# Pico_Primer_Kit_v1_0.net
KiCad netlist of a schematic drawn in EAGLE
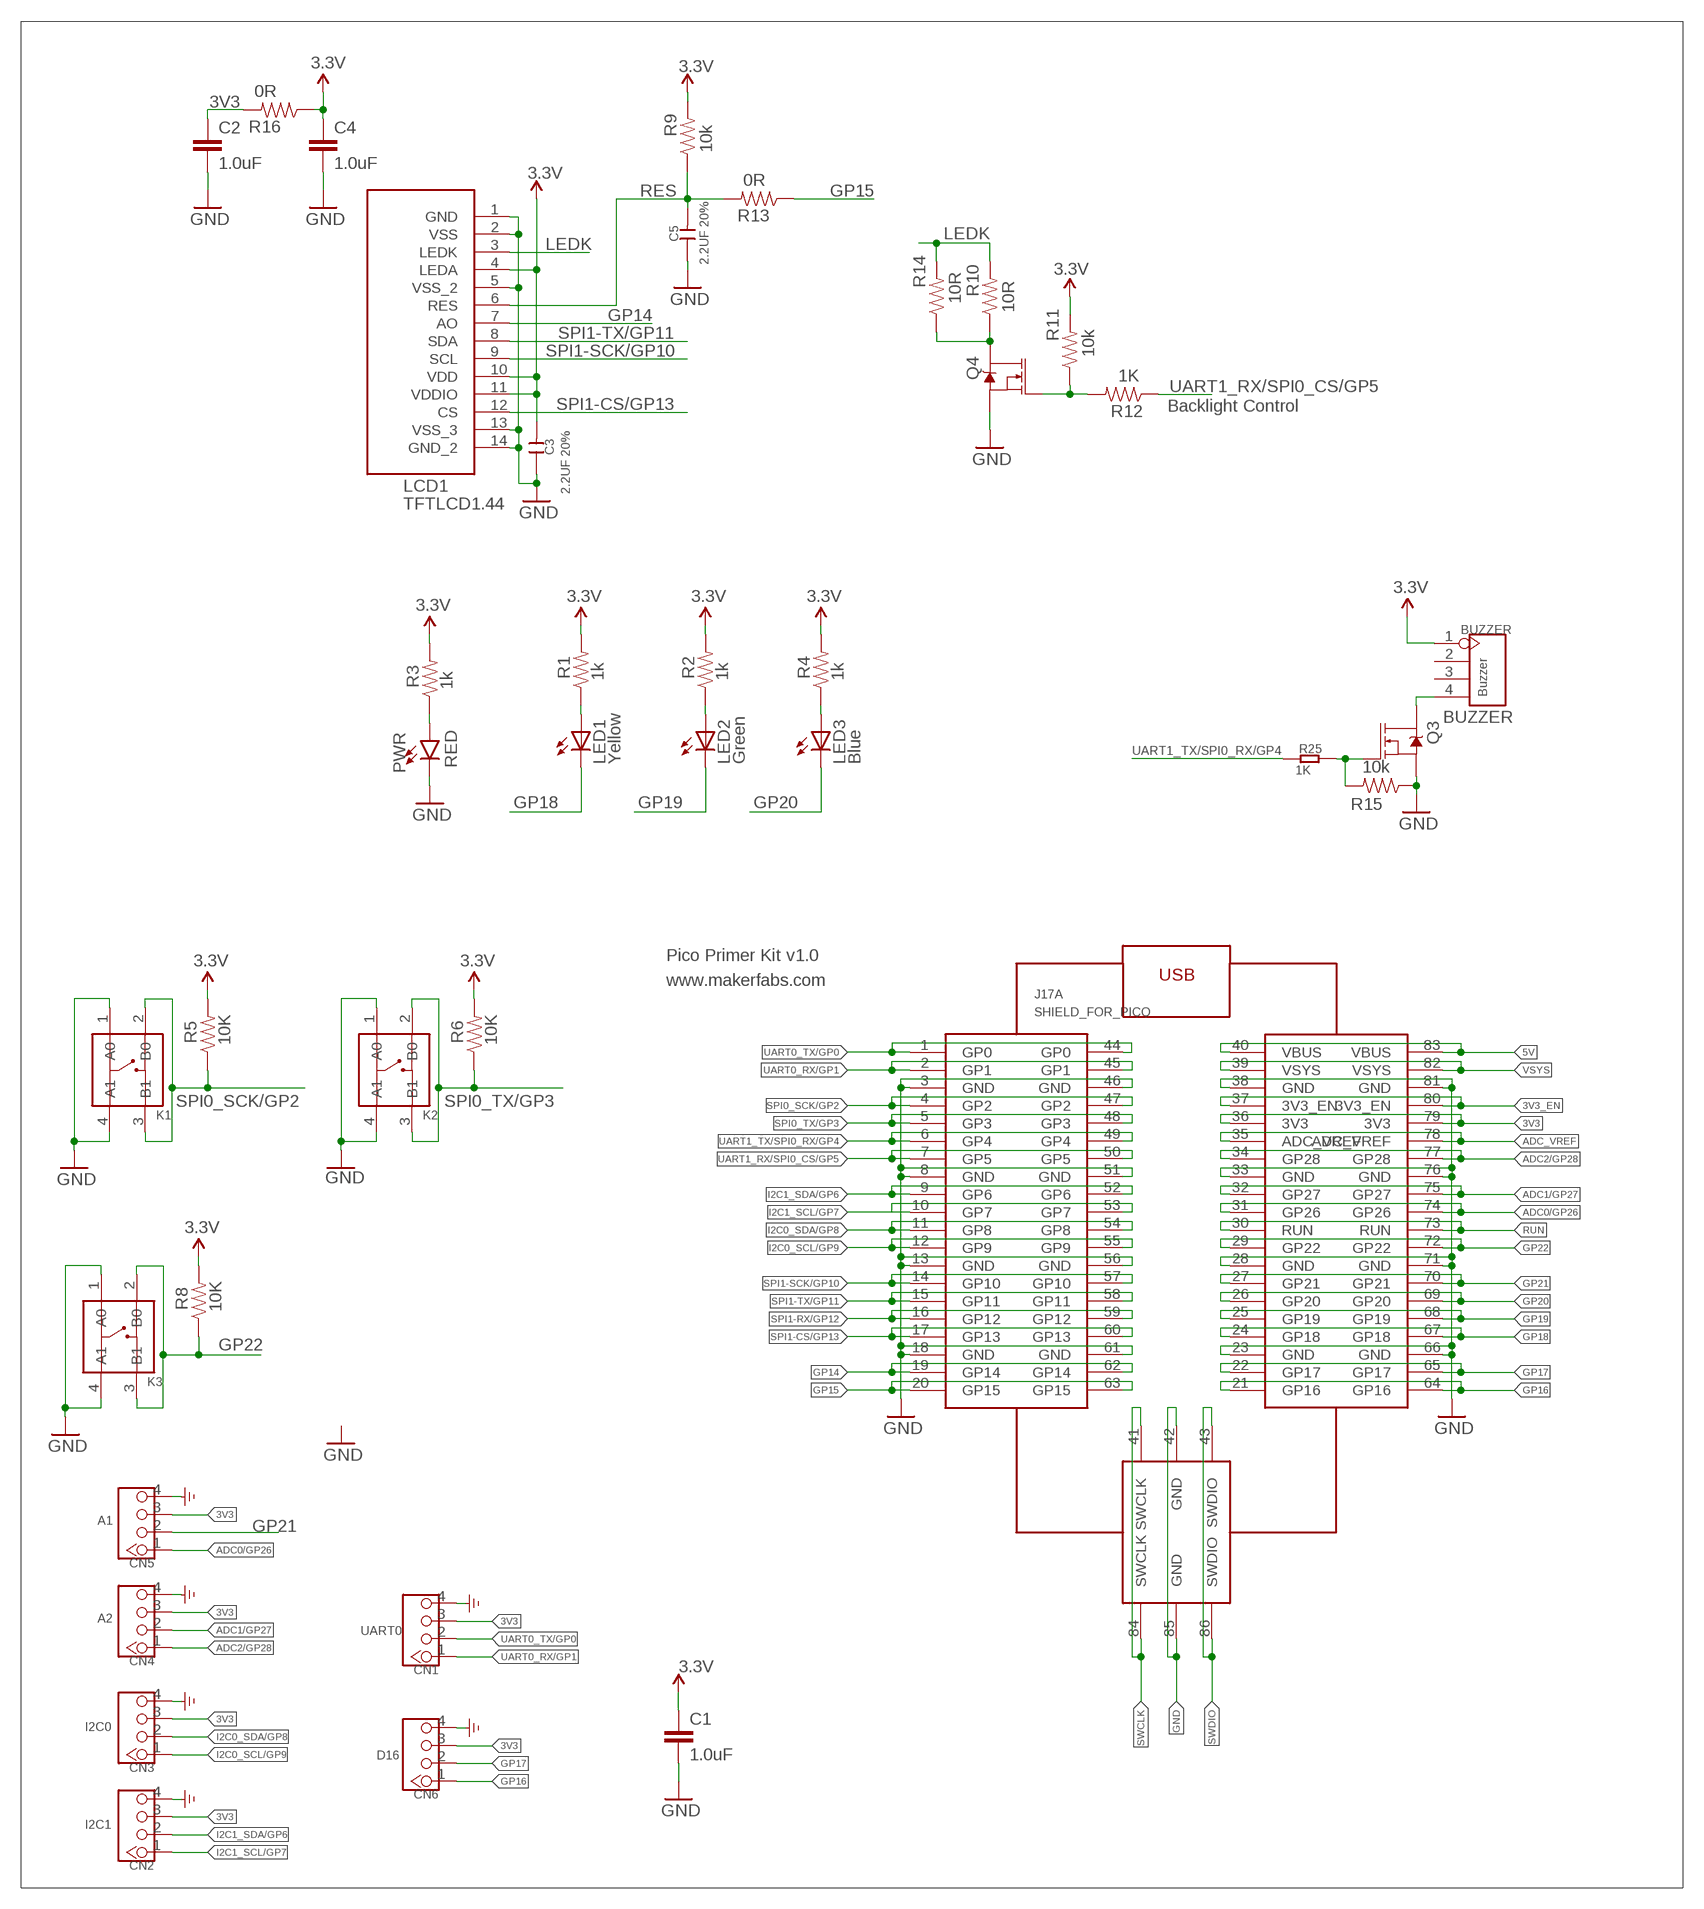
[diagram p0: schematic, sheet 1]

(export (version "E")
  (design (tool "Eeschema 10.0.6"))
  (components
    (comp (ref "BUZZER")
      (value "Buzzer")
      (footprint "eagle-import:4P-65_35ROUND")
      (libsource (lib "eagle-import") (part "HEADER-4P-60/35MILROUND"))
    )
    (comp (ref "C1")
      (value "1.0uF")
      (footprint "eagle-import:0603")
      (libsource (lib "eagle-import") (part "1.0UF-0603-16V-10%"))
    )
    (comp (ref "C2")
      (value "1.0uF")
      (footprint "eagle-import:0603")
      (libsource (lib "eagle-import") (part "1.0UF-0603-16V-10%"))
    )
    (comp (ref "C3")
      (value "2.2UF 20%")
      (footprint "eagle-import:0603")
      (libsource (lib "eagle-import") (part "C-0603"))
    )
    (comp (ref "C4")
      (value "1.0uF")
      (footprint "eagle-import:0603")
      (libsource (lib "eagle-import") (part "1.0UF-0603-16V-10%"))
    )
    (comp (ref "C5")
      (value "2.2UF 20%")
      (footprint "eagle-import:0603")
      (libsource (lib "eagle-import") (part "C-0603"))
    )
    (comp (ref "CN1")
      (value "UART0")
      (footprint "eagle-import:4P-2.0")
      (libsource (lib "eagle-import") (part "TWIG-4P-2.0-2.0"))
    )
    (comp (ref "CN2")
      (value "I2C1")
      (footprint "eagle-import:4P-2.0")
      (libsource (lib "eagle-import") (part "TWIG-4P-2.0-2.0"))
    )
    (comp (ref "CN3")
      (value "I2C0")
      (footprint "eagle-import:4P-2.0")
      (libsource (lib "eagle-import") (part "TWIG-4P-2.0-2.0"))
    )
    (comp (ref "CN4")
      (value "A2")
      (footprint "eagle-import:4P-2.0")
      (libsource (lib "eagle-import") (part "TWIG-4P-2.0-2.0"))
    )
    (comp (ref "CN5")
      (value "A1")
      (footprint "eagle-import:4P-2.0")
      (libsource (lib "eagle-import") (part "TWIG-4P-2.0-2.0"))
    )
    (comp (ref "CN6")
      (value "D16")
      (footprint "eagle-import:4P-2.0")
      (libsource (lib "eagle-import") (part "TWIG-4P-2.0-2.0"))
    )
    (comp (ref "J17A")
      (value "SHIELD_FOR_PICO")
      (footprint "eagle-import:SHIELD_FOR_PICO")
      (libsource (lib "eagle-import") (part "SHIELD_FOR_PICO"))
    )
    (comp (ref "K1")
      (value "BUTTON-4P-3100010P1")
      (footprint "eagle-import:4P-SMD-6.0X6.0X5.0H")
      (libsource (lib "eagle-import") (part "BUTTON-4P-3100010P1"))
    )
    (comp (ref "K2")
      (value "BUTTON-4P-3100010P1")
      (footprint "eagle-import:4P-SMD-6.0X6.0X5.0H")
      (libsource (lib "eagle-import") (part "BUTTON-4P-3100010P1"))
    )
    (comp (ref "K3")
      (value "BUTTON-4P-3100010P1")
      (footprint "eagle-import:4P-SMD-6.0X6.0X5.0H")
      (libsource (lib "eagle-import") (part "BUTTON-4P-3100010P1"))
    )
    (comp (ref "LCD1")
      (value "TFTLCD1.44")
      (footprint "eagle-import:TFTLCD1.44")
      (libsource (lib "eagle-import") (part "TFTLCD1.44"))
    )
    (comp (ref "LED1")
      (value "Yellow")
      (footprint "eagle-import:LED3MM")
      (libsource (lib "eagle-import") (part "LED3MM"))
    )
    (comp (ref "LED2")
      (value "Green")
      (footprint "eagle-import:LED3MM")
      (libsource (lib "eagle-import") (part "LED3MM"))
    )
    (comp (ref "LED3")
      (value "Blue")
      (footprint "eagle-import:LED3MM")
      (libsource (lib "eagle-import") (part "LED3MM"))
    )
    (comp (ref "PWR")
      (value "RED")
      (footprint "eagle-import:LED-0603")
      (libsource (lib "eagle-import") (part "LED-RED0603"))
    )
    (comp (ref "Q3")
      (value "220mA/50V/3.5Ω")
      (footprint "eagle-import:SOT23-3")
      (fields (field (name "PROD_ID") "TRANS-00830"))
      (libsource (lib "eagle-import") (part "MOSFET-NCH-BSS138"))
    )
    (comp (ref "Q4")
      (value "220mA/50V/3.5Ω")
      (footprint "eagle-import:SOT23-3")
      (fields (field (name "PROD_ID") "TRANS-00830"))
      (libsource (lib "eagle-import") (part "MOSFET-NCH-BSS138"))
    )
    (comp (ref "R1")
      (value "1k")
      (footprint "eagle-import:0603")
      (libsource (lib "eagle-import") (part "1KOHM-0603-1/10W-1%"))
    )
    (comp (ref "R2")
      (value "1k")
      (footprint "eagle-import:0603")
      (libsource (lib "eagle-import") (part "1KOHM-0603-1/10W-1%"))
    )
    (comp (ref "R3")
      (value "1k")
      (footprint "eagle-import:0603")
      (libsource (lib "eagle-import") (part "1KOHM-0603-1/10W-1%"))
    )
    (comp (ref "R4")
      (value "1k")
      (footprint "eagle-import:0603")
      (libsource (lib "eagle-import") (part "1KOHM-0603-1/10W-1%"))
    )
    (comp (ref "R5")
      (value "10K")
      (footprint "eagle-import:0603")
      (libsource (lib "eagle-import") (part "1KOHM-0603-1/10W-1%"))
    )
    (comp (ref "R6")
      (value "10K")
      (footprint "eagle-import:0603")
      (libsource (lib "eagle-import") (part "1KOHM-0603-1/10W-1%"))
    )
    (comp (ref "R8")
      (value "10K")
      (footprint "eagle-import:0603")
      (libsource (lib "eagle-import") (part "1KOHM-0603-1/10W-1%"))
    )
    (comp (ref "R9")
      (value "10k")
      (footprint "eagle-import:0603")
      (fields (field (name "PROD_ID") "RES-00824"))
      (libsource (lib "eagle-import") (part "10KOHM-0603-1/10W-1%"))
    )
    (comp (ref "R10")
      (value "10R")
      (footprint "eagle-import:0603")
      (fields (field (name "PROD_ID") "RES-00824"))
      (libsource (lib "eagle-import") (part "10KOHM-0603-1/10W-1%"))
    )
    (comp (ref "R11")
      (value "10k")
      (footprint "eagle-import:0603")
      (fields (field (name "PROD_ID") "RES-00824"))
      (libsource (lib "eagle-import") (part "10KOHM-0603-1/10W-1%"))
    )
    (comp (ref "R12")
      (value "1K")
      (footprint "eagle-import:0603")
      (fields (field (name "PROD_ID") "RES-00824"))
      (libsource (lib "eagle-import") (part "10KOHM-0603-1/10W-1%"))
    )
    (comp (ref "R13")
      (value "0R")
      (footprint "eagle-import:0603")
      (fields (field (name "PROD_ID") "RES-00824"))
      (libsource (lib "eagle-import") (part "10KOHM-0603-1/10W-1%"))
    )
    (comp (ref "R14")
      (value "10R")
      (footprint "eagle-import:0603")
      (fields (field (name "PROD_ID") "RES-00824"))
      (libsource (lib "eagle-import") (part "10KOHM-0603-1/10W-1%"))
    )
    (comp (ref "R15")
      (value "10k")
      (footprint "eagle-import:0603")
      (fields (field (name "PROD_ID") "RES-00824"))
      (libsource (lib "eagle-import") (part "10KOHM-0603-1/10W-1%"))
    )
    (comp (ref "R16")
      (value "0R")
      (footprint "eagle-import:0603")
      (fields (field (name "PROD_ID") "RES-00824"))
      (libsource (lib "eagle-import") (part "10KOHM-0603-1/10W-1%"))
    )
    (comp (ref "R25")
      (value "1K")
      (footprint "eagle-import:R0603")
      (libsource (lib "eagle-import") (part "R-0603"))
    )
  )
  (nets
    (net (code "1") (name "/LEDK") (class "Default")
      (node (ref "LCD1") (pin "3") (pinfunction "LEDK_3") (pintype "bidirectional"))
      (node (ref "R10") (pin "2") (pinfunction "2_2") (pintype "passive"))
      (node (ref "R14") (pin "2") (pinfunction "2_2") (pintype "passive"))
    )
    (net (code "2") (name "/RES") (class "Default")
      (node (ref "C5") (pin "2") (pinfunction "2_2") (pintype "passive"))
      (node (ref "LCD1") (pin "6") (pinfunction "RES_6") (pintype "bidirectional"))
      (node (ref "R13") (pin "2") (pinfunction "2_2") (pintype "passive"))
      (node (ref "R9") (pin "1") (pinfunction "1_1") (pintype "passive"))
    )
    (net (code "3") (name "3.3V") (class "Default")
      (node (ref "BUZZER") (pin "1") (pinfunction "P$1_1") (pintype "bidirectional"))
      (node (ref "C1") (pin "1") (pinfunction "1_1") (pintype "passive"))
      (node (ref "C3") (pin "2") (pinfunction "2_2") (pintype "passive"))
      (node (ref "C4") (pin "1") (pinfunction "1_1") (pintype "passive"))
      (node (ref "LCD1") (pin "10") (pinfunction "VDD_10") (pintype "bidirectional"))
      (node (ref "LCD1") (pin "11") (pinfunction "VDDIO_11") (pintype "bidirectional"))
      (node (ref "LCD1") (pin "4") (pinfunction "LEDA_4") (pintype "bidirectional"))
      (node (ref "R1") (pin "2") (pinfunction "2_2") (pintype "passive"))
      (node (ref "R11") (pin "2") (pinfunction "2_2") (pintype "passive"))
      (node (ref "R16") (pin "1") (pinfunction "1_1") (pintype "passive"))
      (node (ref "R2") (pin "2") (pinfunction "2_2") (pintype "passive"))
      (node (ref "R3") (pin "2") (pinfunction "2_2") (pintype "passive"))
      (node (ref "R4") (pin "2") (pinfunction "2_2") (pintype "passive"))
      (node (ref "R5") (pin "2") (pinfunction "2_2") (pintype "passive"))
      (node (ref "R6") (pin "2") (pinfunction "2_2") (pintype "passive"))
      (node (ref "R8") (pin "2") (pinfunction "2_2") (pintype "passive"))
      (node (ref "R9") (pin "2") (pinfunction "2_2") (pintype "passive"))
    )
    (net (code "4") (name "3V3") (class "Default")
      (node (ref "C2") (pin "1") (pinfunction "1_1") (pintype "passive"))
      (node (ref "CN1") (pin "3") (pinfunction "3_3") (pintype "bidirectional"))
      (node (ref "CN2") (pin "3") (pinfunction "3_3") (pintype "bidirectional"))
      (node (ref "CN3") (pin "3") (pinfunction "3_3") (pintype "bidirectional"))
      (node (ref "CN4") (pin "3") (pinfunction "3_3") (pintype "bidirectional"))
      (node (ref "CN5") (pin "3") (pinfunction "3_3") (pintype "bidirectional"))
      (node (ref "CN6") (pin "3") (pinfunction "3_3") (pintype "bidirectional"))
      (node (ref "J17A") (pin "36") (pinfunction "3V3_36") (pintype "bidirectional"))
      (node (ref "J17A") (pin "79") (pinfunction "3V3_79") (pintype "bidirectional"))
      (node (ref "R16") (pin "2") (pinfunction "2_2") (pintype "passive"))
    )
    (net (code "5") (name "3V3_EN") (class "Default")
      (node (ref "J17A") (pin "37") (pinfunction "3V3_EN_37") (pintype "bidirectional"))
      (node (ref "J17A") (pin "80") (pinfunction "3V3_EN_80") (pintype "bidirectional"))
    )
    (net (code "6") (name "5V") (class "Default")
      (node (ref "J17A") (pin "40") (pinfunction "VBUS_40") (pintype "bidirectional"))
      (node (ref "J17A") (pin "83") (pinfunction "VBUS_83") (pintype "bidirectional"))
    )
    (net (code "7") (name "ADC0{slash}GP26") (class "Default")
      (node (ref "CN5") (pin "1") (pinfunction "1_1") (pintype "bidirectional"))
      (node (ref "J17A") (pin "31") (pinfunction "GP26_31") (pintype "bidirectional"))
      (node (ref "J17A") (pin "74") (pinfunction "GP26_74") (pintype "bidirectional"))
    )
    (net (code "8") (name "ADC1{slash}GP27") (class "Default")
      (node (ref "CN4") (pin "2") (pinfunction "2_2") (pintype "bidirectional"))
      (node (ref "J17A") (pin "32") (pinfunction "GP27_32") (pintype "bidirectional"))
      (node (ref "J17A") (pin "75") (pinfunction "GP27_75") (pintype "bidirectional"))
    )
    (net (code "9") (name "ADC2{slash}GP28") (class "Default")
      (node (ref "CN4") (pin "1") (pinfunction "1_1") (pintype "bidirectional"))
      (node (ref "J17A") (pin "34") (pinfunction "GP28_34") (pintype "bidirectional"))
      (node (ref "J17A") (pin "77") (pinfunction "GP28_77") (pintype "bidirectional"))
    )
    (net (code "10") (name "ADC_VREF") (class "Default")
      (node (ref "J17A") (pin "35") (pinfunction "ADC_VREF_35") (pintype "bidirectional"))
      (node (ref "J17A") (pin "78") (pinfunction "ADC_VREF_78") (pintype "bidirectional"))
    )
    (net (code "11") (name "GND") (class "Default")
      (node (ref "C1") (pin "2") (pinfunction "2_2") (pintype "passive"))
      (node (ref "C2") (pin "2") (pinfunction "2_2") (pintype "passive"))
      (node (ref "C3") (pin "1") (pinfunction "1_1") (pintype "passive"))
      (node (ref "C4") (pin "2") (pinfunction "2_2") (pintype "passive"))
      (node (ref "C5") (pin "1") (pinfunction "1_1") (pintype "passive"))
      (node (ref "CN1") (pin "4") (pinfunction "4_4") (pintype "bidirectional"))
      (node (ref "CN2") (pin "4") (pinfunction "4_4") (pintype "bidirectional"))
      (node (ref "CN3") (pin "4") (pinfunction "4_4") (pintype "bidirectional"))
      (node (ref "CN4") (pin "4") (pinfunction "4_4") (pintype "bidirectional"))
      (node (ref "CN5") (pin "4") (pinfunction "4_4") (pintype "bidirectional"))
      (node (ref "CN6") (pin "4") (pinfunction "4_4") (pintype "bidirectional"))
      (node (ref "J17A") (pin "13") (pinfunction "GND_13") (pintype "bidirectional"))
      (node (ref "J17A") (pin "18") (pinfunction "GND_18") (pintype "bidirectional"))
      (node (ref "J17A") (pin "23") (pinfunction "GND_23") (pintype "bidirectional"))
      (node (ref "J17A") (pin "28") (pinfunction "GND_28") (pintype "bidirectional"))
      (node (ref "J17A") (pin "3") (pinfunction "GND_3") (pintype "bidirectional"))
      (node (ref "J17A") (pin "33") (pinfunction "GND_33") (pintype "bidirectional"))
      (node (ref "J17A") (pin "38") (pinfunction "GND_38") (pintype "bidirectional"))
      (node (ref "J17A") (pin "42") (pinfunction "GND_42") (pintype "bidirectional"))
      (node (ref "J17A") (pin "46") (pinfunction "GND_46") (pintype "bidirectional"))
      (node (ref "J17A") (pin "51") (pinfunction "GND_51") (pintype "bidirectional"))
      (node (ref "J17A") (pin "56") (pinfunction "GND_56") (pintype "bidirectional"))
      (node (ref "J17A") (pin "61") (pinfunction "GND_61") (pintype "bidirectional"))
      (node (ref "J17A") (pin "66") (pinfunction "GND_66") (pintype "bidirectional"))
      (node (ref "J17A") (pin "71") (pinfunction "GND_71") (pintype "bidirectional"))
      (node (ref "J17A") (pin "76") (pinfunction "GND_76") (pintype "bidirectional"))
      (node (ref "J17A") (pin "8") (pinfunction "GND_8") (pintype "bidirectional"))
      (node (ref "J17A") (pin "81") (pinfunction "GND_81") (pintype "bidirectional"))
      (node (ref "J17A") (pin "85") (pinfunction "GND_85") (pintype "bidirectional"))
      (node (ref "K1") (pin "1") (pinfunction "A0_1") (pintype "bidirectional"))
      (node (ref "K1") (pin "4") (pinfunction "A1_4") (pintype "bidirectional"))
      (node (ref "K2") (pin "1") (pinfunction "A0_1") (pintype "bidirectional"))
      (node (ref "K2") (pin "4") (pinfunction "A1_4") (pintype "bidirectional"))
      (node (ref "K3") (pin "1") (pinfunction "A0_1") (pintype "bidirectional"))
      (node (ref "K3") (pin "4") (pinfunction "A1_4") (pintype "bidirectional"))
      (node (ref "LCD1") (pin "1") (pinfunction "GND_1") (pintype "bidirectional"))
      (node (ref "LCD1") (pin "13") (pinfunction "VSS_3_13") (pintype "bidirectional"))
      (node (ref "LCD1") (pin "14") (pinfunction "GND_2_14") (pintype "bidirectional"))
      (node (ref "LCD1") (pin "2") (pinfunction "VSS_2") (pintype "bidirectional"))
      (node (ref "LCD1") (pin "5") (pinfunction "VSS_2_5") (pintype "bidirectional"))
      (node (ref "PWR") (pin "C") (pinfunction "C_C") (pintype "passive"))
      (node (ref "Q3") (pin "2") (pinfunction "S_2") (pintype "bidirectional"))
      (node (ref "Q4") (pin "2") (pinfunction "S_2") (pintype "bidirectional"))
      (node (ref "R15") (pin "1") (pinfunction "1_1") (pintype "passive"))
    )
    (net (code "12") (name "GP14") (class "Default")
      (node (ref "J17A") (pin "19") (pinfunction "GP14_19") (pintype "bidirectional"))
      (node (ref "J17A") (pin "62") (pinfunction "GP14_62") (pintype "bidirectional"))
      (node (ref "LCD1") (pin "7") (pinfunction "AO_7") (pintype "bidirectional"))
    )
    (net (code "13") (name "GP15") (class "Default")
      (node (ref "J17A") (pin "20") (pinfunction "GP15_20") (pintype "bidirectional"))
      (node (ref "J17A") (pin "63") (pinfunction "GP15_63") (pintype "bidirectional"))
      (node (ref "R13") (pin "1") (pinfunction "1_1") (pintype "passive"))
    )
    (net (code "14") (name "GP16") (class "Default")
      (node (ref "CN6") (pin "1") (pinfunction "1_1") (pintype "bidirectional"))
      (node (ref "J17A") (pin "21") (pinfunction "GP16_21") (pintype "bidirectional"))
      (node (ref "J17A") (pin "64") (pinfunction "GP16_64") (pintype "bidirectional"))
    )
    (net (code "15") (name "GP17") (class "Default")
      (node (ref "CN6") (pin "2") (pinfunction "2_2") (pintype "bidirectional"))
      (node (ref "J17A") (pin "22") (pinfunction "GP17_22") (pintype "bidirectional"))
      (node (ref "J17A") (pin "65") (pinfunction "GP17_65") (pintype "bidirectional"))
    )
    (net (code "16") (name "GP18") (class "Default")
      (node (ref "J17A") (pin "24") (pinfunction "GP18_24") (pintype "bidirectional"))
      (node (ref "J17A") (pin "67") (pinfunction "GP18_67") (pintype "bidirectional"))
      (node (ref "LED1") (pin "K") (pinfunction "C_K") (pintype "passive"))
    )
    (net (code "17") (name "GP19") (class "Default")
      (node (ref "J17A") (pin "25") (pinfunction "GP19_25") (pintype "bidirectional"))
      (node (ref "J17A") (pin "68") (pinfunction "GP19_68") (pintype "bidirectional"))
      (node (ref "LED2") (pin "K") (pinfunction "C_K") (pintype "passive"))
    )
    (net (code "18") (name "GP20") (class "Default")
      (node (ref "J17A") (pin "26") (pinfunction "GP20_26") (pintype "bidirectional"))
      (node (ref "J17A") (pin "69") (pinfunction "GP20_69") (pintype "bidirectional"))
      (node (ref "LED3") (pin "K") (pinfunction "C_K") (pintype "passive"))
    )
    (net (code "19") (name "GP21") (class "Default")
      (node (ref "CN5") (pin "2") (pinfunction "2_2") (pintype "bidirectional"))
      (node (ref "J17A") (pin "27") (pinfunction "GP21_27") (pintype "bidirectional"))
      (node (ref "J17A") (pin "70") (pinfunction "GP21_70") (pintype "bidirectional"))
    )
    (net (code "20") (name "GP22") (class "Default")
      (node (ref "J17A") (pin "29") (pinfunction "GP22_29") (pintype "bidirectional"))
      (node (ref "J17A") (pin "72") (pinfunction "GP22_72") (pintype "bidirectional"))
      (node (ref "K3") (pin "2") (pinfunction "B0_2") (pintype "bidirectional"))
      (node (ref "K3") (pin "3") (pinfunction "B1_3") (pintype "bidirectional"))
      (node (ref "R8") (pin "1") (pinfunction "1_1") (pintype "passive"))
    )
    (net (code "21") (name "I2C0_SCL{slash}GP9") (class "Default")
      (node (ref "CN3") (pin "1") (pinfunction "1_1") (pintype "bidirectional"))
      (node (ref "J17A") (pin "12") (pinfunction "GP9_12") (pintype "bidirectional"))
      (node (ref "J17A") (pin "55") (pinfunction "GP9_55") (pintype "bidirectional"))
    )
    (net (code "22") (name "I2C0_SDA{slash}GP8") (class "Default")
      (node (ref "CN3") (pin "2") (pinfunction "2_2") (pintype "bidirectional"))
      (node (ref "J17A") (pin "11") (pinfunction "GP8_11") (pintype "bidirectional"))
      (node (ref "J17A") (pin "54") (pinfunction "GP8_54") (pintype "bidirectional"))
    )
    (net (code "23") (name "I2C1_SCL{slash}GP7") (class "Default")
      (node (ref "CN2") (pin "1") (pinfunction "1_1") (pintype "bidirectional"))
      (node (ref "J17A") (pin "10") (pinfunction "GP7_10") (pintype "bidirectional"))
      (node (ref "J17A") (pin "53") (pinfunction "GP7_53") (pintype "bidirectional"))
    )
    (net (code "24") (name "I2C1_SDA{slash}GP6") (class "Default")
      (node (ref "CN2") (pin "2") (pinfunction "2_2") (pintype "bidirectional"))
      (node (ref "J17A") (pin "52") (pinfunction "GP6_52") (pintype "bidirectional"))
      (node (ref "J17A") (pin "9") (pinfunction "GP6_9") (pintype "bidirectional"))
    )
    (net (code "25") (name "Net-(BUZZER-P$4)") (class "Default")
      (node (ref "BUZZER") (pin "4") (pinfunction "P$4_4") (pintype "bidirectional"))
      (node (ref "Q3") (pin "3") (pinfunction "D_3") (pintype "bidirectional"))
    )
    (net (code "26") (name "Net-(LED1-PadA)") (class "Default")
      (node (ref "LED1") (pin "A") (pinfunction "A_A") (pintype "passive"))
      (node (ref "R1") (pin "1") (pinfunction "1_1") (pintype "passive"))
    )
    (net (code "27") (name "Net-(LED2-PadA)") (class "Default")
      (node (ref "LED2") (pin "A") (pinfunction "A_A") (pintype "passive"))
      (node (ref "R2") (pin "1") (pinfunction "1_1") (pintype "passive"))
    )
    (net (code "28") (name "Net-(LED3-PadA)") (class "Default")
      (node (ref "LED3") (pin "A") (pinfunction "A_A") (pintype "passive"))
      (node (ref "R4") (pin "1") (pinfunction "1_1") (pintype "passive"))
    )
    (net (code "29") (name "Net-(PWR-PadA)") (class "Default")
      (node (ref "PWR") (pin "A") (pinfunction "A_A") (pintype "passive"))
      (node (ref "R3") (pin "1") (pinfunction "1_1") (pintype "passive"))
    )
    (net (code "30") (name "Net-(Q3-G)") (class "Default")
      (node (ref "Q3") (pin "1") (pinfunction "G_1") (pintype "bidirectional"))
      (node (ref "R15") (pin "2") (pinfunction "2_2") (pintype "passive"))
      (node (ref "R25") (pin "2") (pinfunction "2_2") (pintype "passive"))
    )
    (net (code "31") (name "Net-(Q4-D)") (class "Default")
      (node (ref "Q4") (pin "3") (pinfunction "D_3") (pintype "bidirectional"))
      (node (ref "R10") (pin "1") (pinfunction "1_1") (pintype "passive"))
      (node (ref "R14") (pin "1") (pinfunction "1_1") (pintype "passive"))
    )
    (net (code "32") (name "Net-(Q4-G)") (class "Default")
      (node (ref "Q4") (pin "1") (pinfunction "G_1") (pintype "bidirectional"))
      (node (ref "R11") (pin "1") (pinfunction "1_1") (pintype "passive"))
      (node (ref "R12") (pin "2") (pinfunction "2_2") (pintype "passive"))
    )
    (net (code "33") (name "RUN") (class "Default")
      (node (ref "J17A") (pin "30") (pinfunction "RUN_30") (pintype "bidirectional"))
      (node (ref "J17A") (pin "73") (pinfunction "RUN_73") (pintype "bidirectional"))
    )
    (net (code "34") (name "SPI0_SCK{slash}GP2") (class "Default")
      (node (ref "J17A") (pin "4") (pinfunction "GP2_4") (pintype "bidirectional"))
      (node (ref "J17A") (pin "47") (pinfunction "GP2_47") (pintype "bidirectional"))
      (node (ref "K1") (pin "2") (pinfunction "B0_2") (pintype "bidirectional"))
      (node (ref "K1") (pin "3") (pinfunction "B1_3") (pintype "bidirectional"))
      (node (ref "R5") (pin "1") (pinfunction "1_1") (pintype "passive"))
    )
    (net (code "35") (name "SPI0_TX{slash}GP3") (class "Default")
      (node (ref "J17A") (pin "48") (pinfunction "GP3_48") (pintype "bidirectional"))
      (node (ref "J17A") (pin "5") (pinfunction "GP3_5") (pintype "bidirectional"))
      (node (ref "K2") (pin "2") (pinfunction "B0_2") (pintype "bidirectional"))
      (node (ref "K2") (pin "3") (pinfunction "B1_3") (pintype "bidirectional"))
      (node (ref "R6") (pin "1") (pinfunction "1_1") (pintype "passive"))
    )
    (net (code "36") (name "SPI1-CS{slash}GP13") (class "Default")
      (node (ref "J17A") (pin "17") (pinfunction "GP13_17") (pintype "bidirectional"))
      (node (ref "J17A") (pin "60") (pinfunction "GP13_60") (pintype "bidirectional"))
      (node (ref "LCD1") (pin "12") (pinfunction "CS_12") (pintype "bidirectional"))
    )
    (net (code "37") (name "SPI1-RX{slash}GP12") (class "Default")
      (node (ref "J17A") (pin "16") (pinfunction "GP12_16") (pintype "bidirectional"))
      (node (ref "J17A") (pin "59") (pinfunction "GP12_59") (pintype "bidirectional"))
    )
    (net (code "38") (name "SPI1-SCK{slash}GP10") (class "Default")
      (node (ref "J17A") (pin "14") (pinfunction "GP10_14") (pintype "bidirectional"))
      (node (ref "J17A") (pin "57") (pinfunction "GP10_57") (pintype "bidirectional"))
      (node (ref "LCD1") (pin "9") (pinfunction "SCL_9") (pintype "bidirectional"))
    )
    (net (code "39") (name "SPI1-TX{slash}GP11") (class "Default")
      (node (ref "J17A") (pin "15") (pinfunction "GP11_15") (pintype "bidirectional"))
      (node (ref "J17A") (pin "58") (pinfunction "GP11_58") (pintype "bidirectional"))
      (node (ref "LCD1") (pin "8") (pinfunction "SDA_8") (pintype "bidirectional"))
    )
    (net (code "40") (name "SWCLK") (class "Default")
      (node (ref "J17A") (pin "41") (pinfunction "SWCLK_41") (pintype "bidirectional"))
      (node (ref "J17A") (pin "84") (pinfunction "SWCLK_84") (pintype "bidirectional"))
    )
    (net (code "41") (name "SWDIO") (class "Default")
      (node (ref "J17A") (pin "43") (pinfunction "SWDIO_43") (pintype "bidirectional"))
      (node (ref "J17A") (pin "86") (pinfunction "SWDIO_86") (pintype "bidirectional"))
    )
    (net (code "42") (name "UART0_RX{slash}GP1") (class "Default")
      (node (ref "CN1") (pin "1") (pinfunction "1_1") (pintype "bidirectional"))
      (node (ref "J17A") (pin "2") (pinfunction "GP1_2") (pintype "bidirectional"))
      (node (ref "J17A") (pin "45") (pinfunction "GP1_45") (pintype "bidirectional"))
    )
    (net (code "43") (name "UART0_TX{slash}GP0") (class "Default")
      (node (ref "CN1") (pin "2") (pinfunction "2_2") (pintype "bidirectional"))
      (node (ref "J17A") (pin "1") (pinfunction "GP0_1") (pintype "bidirectional"))
      (node (ref "J17A") (pin "44") (pinfunction "GP0_44") (pintype "bidirectional"))
    )
    (net (code "44") (name "UART1_RX{slash}SPI0_CS{slash}GP5") (class "Default")
      (node (ref "J17A") (pin "50") (pinfunction "GP5_50") (pintype "bidirectional"))
      (node (ref "J17A") (pin "7") (pinfunction "GP5_7") (pintype "bidirectional"))
      (node (ref "R12") (pin "1") (pinfunction "1_1") (pintype "passive"))
    )
    (net (code "45") (name "UART1_TX{slash}SPI0_RX{slash}GP4") (class "Default")
      (node (ref "J17A") (pin "49") (pinfunction "GP4_49") (pintype "bidirectional"))
      (node (ref "J17A") (pin "6") (pinfunction "GP4_6") (pintype "bidirectional"))
      (node (ref "R25") (pin "1") (pinfunction "1_1") (pintype "passive"))
    )
    (net (code "46") (name "VSYS") (class "Default")
      (node (ref "J17A") (pin "39") (pinfunction "VSYS_39") (pintype "bidirectional"))
      (node (ref "J17A") (pin "82") (pinfunction "VSYS_82") (pintype "bidirectional"))
    )
    (net (code "47") (name "unconnected-(BUZZER-P$2-Pad2)") (class "Default")
      (node (ref "BUZZER") (pin "2") (pinfunction "P$2_2") (pintype "bidirectional"))
    )
    (net (code "48") (name "unconnected-(BUZZER-P$3-Pad3)") (class "Default")
      (node (ref "BUZZER") (pin "3") (pinfunction "P$3_3") (pintype "bidirectional"))
    )
  )
)
